# Atividade2Prototipagem.net
KiCad netlist of a schematic drawn in EAGLE
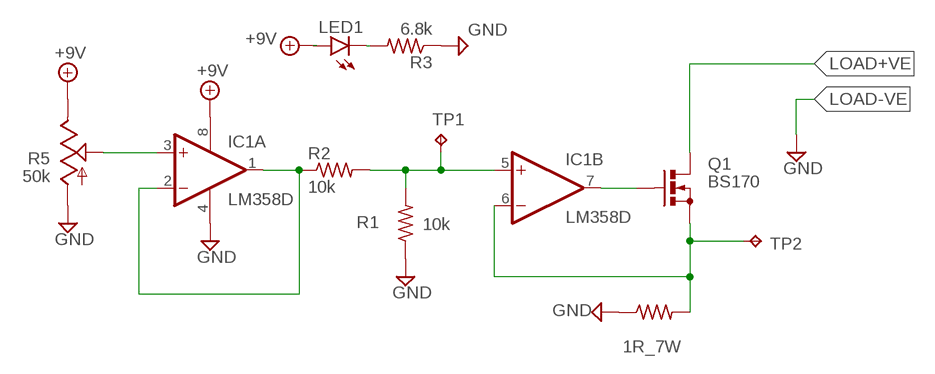
[diagram p0: schematic, sheet 1]

(export (version "E")
  (design (tool "Eeschema 10.0.6"))
  (components
    (comp (ref "1R_7W")
      (value "R-US_0207/10")
      (footprint "eagle-import:0207_10")
      (libsource (lib "eagle-import") (part "R-US_0207/10"))
    )
    (comp (ref "IC1")
      (value "LM358D")
      (footprint "eagle-import:SO08")
      (libsource (lib "eagle-import") (part "LM358D"))
    )
    (comp (ref "LED1")
      (value "LED")
      (footprint "eagle-import:SMARTLED-TTW")
      (libsource (lib "eagle-import") (part "LED"))
    )
    (comp (ref "Q1")
      (value "BS170")
      (footprint "eagle-import:SOT54E")
      (libsource (lib "eagle-import") (part "BS170"))
    )
    (comp (ref "R1")
      (value "10k")
      (footprint "eagle-import:0207_10")
      (libsource (lib "eagle-import") (part "R-US_0207/10"))
    )
    (comp (ref "R2")
      (value "10k")
      (footprint "eagle-import:0207_10")
      (libsource (lib "eagle-import") (part "R-US_0207/10"))
    )
    (comp (ref "R3")
      (value "6.8k")
      (footprint "eagle-import:0207_10")
      (libsource (lib "eagle-import") (part "R-US_0207/10"))
    )
    (comp (ref "R5")
      (value "50k")
      (footprint "eagle-import:3223J")
      (libsource (lib "eagle-import") (part "TRIM_US-3223J"))
    )
    (comp (ref "TP1")
      (value "TPB1,27")
      (footprint "eagle-import:B1,27")
      (libsource (lib "eagle-import") (part "TPB1,27"))
    )
    (comp (ref "TP2")
      (value "TPB1,27")
      (footprint "eagle-import:B1,27")
      (libsource (lib "eagle-import") (part "TPB1,27"))
    )
  )
  (nets
    (net (code "1") (name "+9V") (class "Default")
      (node (ref "IC1") (pin "8") (pinfunction "V+_8") (pintype "power_in"))
      (node (ref "LED1") (pin "A@1") (pinfunction "A_A@1") (pintype "passive"))
      (node (ref "R5") (pin "3") (pinfunction "E_3") (pintype "passive"))
    )
    (net (code "2") (name "LOAD+VE") (class "Default")
      (node (ref "Q1") (pin "D") (pinfunction "D_D") (pintype "passive"))
    )
    (net (code "3") (name "LOAD-VE") (class "Default")
      (node (ref "1R_7W") (pin "1") (pinfunction "1_1") (pintype "passive"))
      (node (ref "IC1") (pin "4") (pinfunction "V-_4") (pintype "power_in"))
      (node (ref "R1") (pin "1") (pinfunction "1_1") (pintype "passive"))
      (node (ref "R3") (pin "1") (pinfunction "1_1") (pintype "passive"))
      (node (ref "R5") (pin "1") (pinfunction "A_1") (pintype "passive"))
    )
    (net (code "4") (name "Net-(IC1A-+IN)") (class "Default")
      (node (ref "IC1") (pin "3") (pinfunction "+IN_3") (pintype "input"))
      (node (ref "R5") (pin "2") (pinfunction "S_2") (pintype "passive"))
    )
    (net (code "5") (name "Net-(IC1A--IN)") (class "Default")
      (node (ref "IC1") (pin "1") (pinfunction "OUT_1") (pintype "output"))
      (node (ref "IC1") (pin "2") (pinfunction "-IN_2") (pintype "input"))
      (node (ref "R2") (pin "1") (pinfunction "1_1") (pintype "passive"))
    )
    (net (code "6") (name "Net-(IC1B-+IN)") (class "Default")
      (node (ref "IC1") (pin "5") (pinfunction "+IN_5") (pintype "input"))
      (node (ref "R1") (pin "2") (pinfunction "2_2") (pintype "passive"))
      (node (ref "R2") (pin "2") (pinfunction "2_2") (pintype "passive"))
      (node (ref "TP1") (pin "TP") (pinfunction "TP_TP") (pintype "input"))
    )
    (net (code "7") (name "Net-(IC1B--IN)") (class "Default")
      (node (ref "1R_7W") (pin "2") (pinfunction "2_2") (pintype "passive"))
      (node (ref "IC1") (pin "6") (pinfunction "-IN_6") (pintype "input"))
      (node (ref "Q1") (pin "S") (pinfunction "S_S") (pintype "passive"))
      (node (ref "TP2") (pin "TP") (pinfunction "TP_TP") (pintype "input"))
    )
    (net (code "8") (name "Net-(IC1B-OUT)") (class "Default")
      (node (ref "IC1") (pin "7") (pinfunction "OUT_7") (pintype "output"))
      (node (ref "Q1") (pin "G") (pinfunction "G_G") (pintype "passive"))
    )
    (net (code "9") (name "Net-(LED1-C)") (class "Default")
      (node (ref "LED1") (pin "C@1") (pinfunction "C_C@1") (pintype "passive"))
      (node (ref "R3") (pin "2") (pinfunction "2_2") (pintype "passive"))
    )
  )
)
